# NFC_Access_IO_R00.net
KiCad netlist of a schematic drawn in Altium Designer
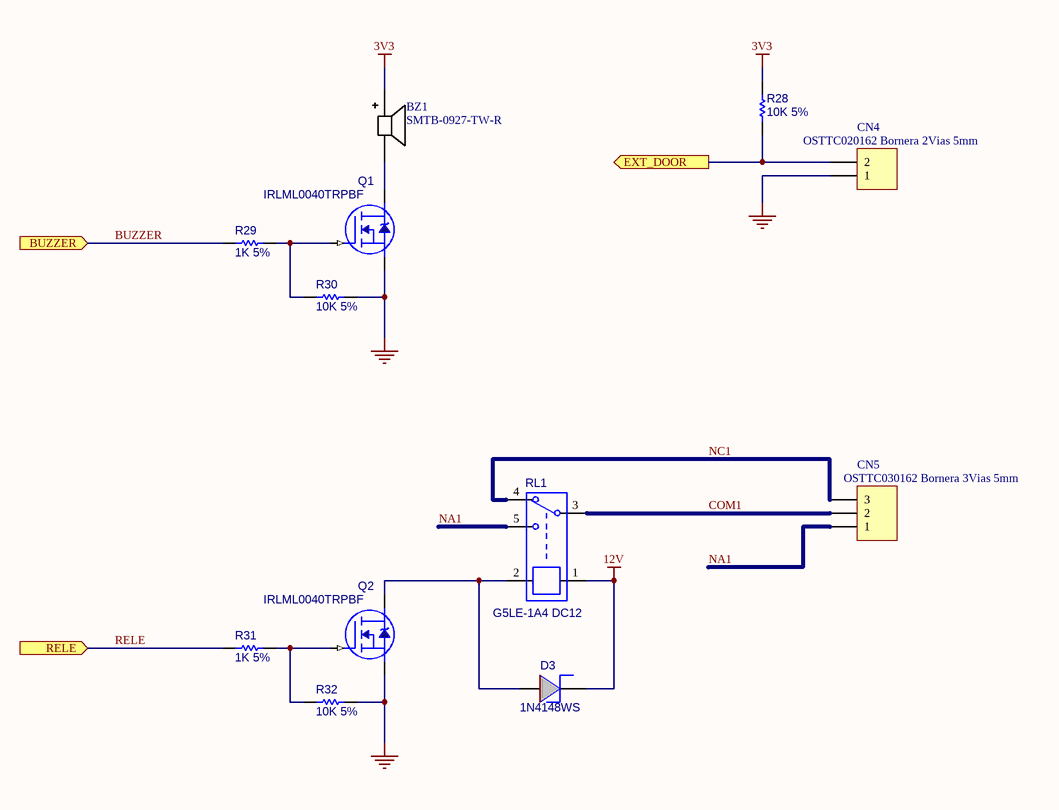
[diagram p0: NFC_Access_IO_R00.SchDoc]

(export (version "E")
  (design (tool "Eeschema 10.0.6"))
  (components
    (comp (ref "BZ1")
      (value "SMTB-0927-TW-R")
      (footprint "SMTB-0927-TW-R")
      (description "3V3 Active Buzzer\r\n668-SMTB-0927-TW-RTR-ND")
      (libsource (lib "NFC_Access_Lib") (part "Buzzer"))
    )
    (comp (ref "CN4")
      (value "OSTTC020162 Bornera 2Vias 5mm")
      (footprint "TerminalBlock_1x2_P5mm")
      (description "TERM BLK 2POS SIDE ENTRY 5MM PCB\r\nED2600-ND")
      (libsource (lib "NFC_Access_Lib") (part "CONN_02P"))
    )
    (comp (ref "CN5")
      (value "OSTTC030162 Bornera 3Vias 5mm")
      (footprint "TerminalBlock_1x3_P5mm")
      (description "TERM BLK 3POS SIDE ENTRY 5MM PCB\r\nED2601-ND")
      (libsource (lib "WiFiNode_R00") (part "CONN_03P"))
    )
    (comp (ref "D3")
      (value "1N4148WS")
      (footprint "SOD_323")
      (description "DIODE GEN PURP 75V 300MA SOD323\r\n1655-1N4148WSTR-ND")
      (libsource (lib "WiFiNode_R00") (part "DIODO_SH"))
    )
    (comp (ref "Q1")
      (value "IRLML0040TRPBF")
      (footprint "SOT_23")
      (description "Mosfet N-Ch\r\nIRLML0040TRPBFTR-ND")
      (libsource (lib "WiFiNode_R00") (part "N_MOSFET_SOT23"))
    )
    (comp (ref "Q2")
      (value "IRLML0040TRPBF")
      (footprint "SOT_23")
      (description "Mosfet N-Ch\r\nIRLML0040TRPBFTR-ND")
      (libsource (lib "WiFiNode_R00") (part "N_MOSFET_SOT23"))
    )
    (comp (ref "R28")
      (value "10K 5%")
      (footprint "R_0603")
      (description "Resistor\r\nCR0603-JW-103ELFTR-ND")
      (libsource (lib "NFC_Access_Lib") (part "Res1"))
    )
    (comp (ref "R29")
      (value "1K 5%")
      (footprint "R_0603")
      (description "Resistor\r\nCR0603-JW-102ELFTR-ND")
      (libsource (lib "WiFiNode_R00") (part "Res1"))
    )
    (comp (ref "R30")
      (value "10K 5%")
      (footprint "R_0603")
      (description "Resistor\r\nCR0603-JW-103ELFTR-ND")
      (libsource (lib "WiFiNode_R00") (part "Res1"))
    )
    (comp (ref "R31")
      (value "1K 5%")
      (footprint "R_0603")
      (description "Resistor\r\nCR0603-JW-102ELFTR-ND")
      (libsource (lib "WiFiNode_R00") (part "Res1"))
    )
    (comp (ref "R32")
      (value "10K 5%")
      (footprint "R_0603")
      (description "Resistor\r\nCR0603-JW-103ELFTR-ND")
      (libsource (lib "WiFiNode_R00") (part "Res1"))
    )
    (comp (ref "RL1")
      (value "G5LE-1A4 DC12")
      (footprint "G5LE-1")
      (description "RELAY GEN PURPOSE SPST 10A 12V\r\nZ2352-ND")
      (libsource (lib "WiFiNode_R00") (part "RELAY SPDT"))
    )
  )
  (nets
    (net (code "1") (name "/BUZZER") (class "Default")
      (node (ref "R29") (pin "2") (pinfunction "2_2") (pintype "passive"))
    )
    (net (code "2") (name "/COM1") (class "Default")
      (node (ref "CN5") (pin "2") (pinfunction "2_2") (pintype "passive"))
      (node (ref "RL1") (pin "3") (pinfunction "3_3") (pintype "passive"))
    )
    (net (code "3") (name "/EXT_DOOR") (class "Default")
      (node (ref "CN4") (pin "2") (pinfunction "2_2") (pintype "passive"))
      (node (ref "R28") (pin "1") (pinfunction "1_1") (pintype "passive"))
    )
    (net (code "4") (name "/NA1") (class "Default")
      (node (ref "CN5") (pin "1") (pinfunction "1_1") (pintype "passive"))
      (node (ref "RL1") (pin "5") (pinfunction "5_5") (pintype "passive"))
    )
    (net (code "5") (name "/NC1") (class "Default")
      (node (ref "CN5") (pin "3") (pinfunction "3_3") (pintype "passive"))
      (node (ref "RL1") (pin "4") (pinfunction "4_4") (pintype "passive"))
    )
    (net (code "6") (name "/RELE") (class "Default")
      (node (ref "R31") (pin "2") (pinfunction "2_2") (pintype "passive"))
    )
    (net (code "7") (name "3V3") (class "Default")
      (node (ref "BZ1") (pin "1") (pinfunction "1_1") (pintype "passive"))
      (node (ref "R28") (pin "2") (pinfunction "2_2") (pintype "passive"))
    )
    (net (code "8") (name "12V") (class "Default")
      (node (ref "D3") (pin "2") (pinfunction "K_2") (pintype "passive"))
      (node (ref "RL1") (pin "1") (pinfunction "1_1") (pintype "passive"))
    )
    (net (code "9") (name "GND") (class "Default")
      (node (ref "CN4") (pin "1") (pinfunction "1_1") (pintype "passive"))
      (node (ref "Q1") (pin "2") (pinfunction "SOURCE_2") (pintype "passive"))
      (node (ref "Q2") (pin "2") (pinfunction "SOURCE_2") (pintype "passive"))
      (node (ref "R30") (pin "1") (pinfunction "1_1") (pintype "passive"))
      (node (ref "R32") (pin "1") (pinfunction "1_1") (pintype "passive"))
    )
    (net (code "10") (name "Net-(D3-A)") (class "Default")
      (node (ref "D3") (pin "1") (pinfunction "A_1") (pintype "passive"))
      (node (ref "Q2") (pin "3") (pinfunction "DRAIN_3") (pintype "passive"))
      (node (ref "RL1") (pin "2") (pinfunction "2_2") (pintype "passive"))
    )
    (net (code "11") (name "Net-(Q1-DRAIN)") (class "Default")
      (node (ref "BZ1") (pin "2") (pinfunction "2_2") (pintype "passive"))
      (node (ref "Q1") (pin "3") (pinfunction "DRAIN_3") (pintype "passive"))
    )
    (net (code "12") (name "Net-(Q1-GATE)") (class "Default")
      (node (ref "Q1") (pin "1") (pinfunction "GATE_1") (pintype "input"))
      (node (ref "R29") (pin "1") (pinfunction "1_1") (pintype "passive"))
      (node (ref "R30") (pin "2") (pinfunction "2_2") (pintype "passive"))
    )
    (net (code "13") (name "Net-(Q2-GATE)") (class "Default")
      (node (ref "Q2") (pin "1") (pinfunction "GATE_1") (pintype "input"))
      (node (ref "R31") (pin "1") (pinfunction "1_1") (pintype "passive"))
      (node (ref "R32") (pin "2") (pinfunction "2_2") (pintype "passive"))
    )
  )
)
